# 03_-_ALIMENTACAO.net
KiCad netlist of a schematic drawn in Altium Designer
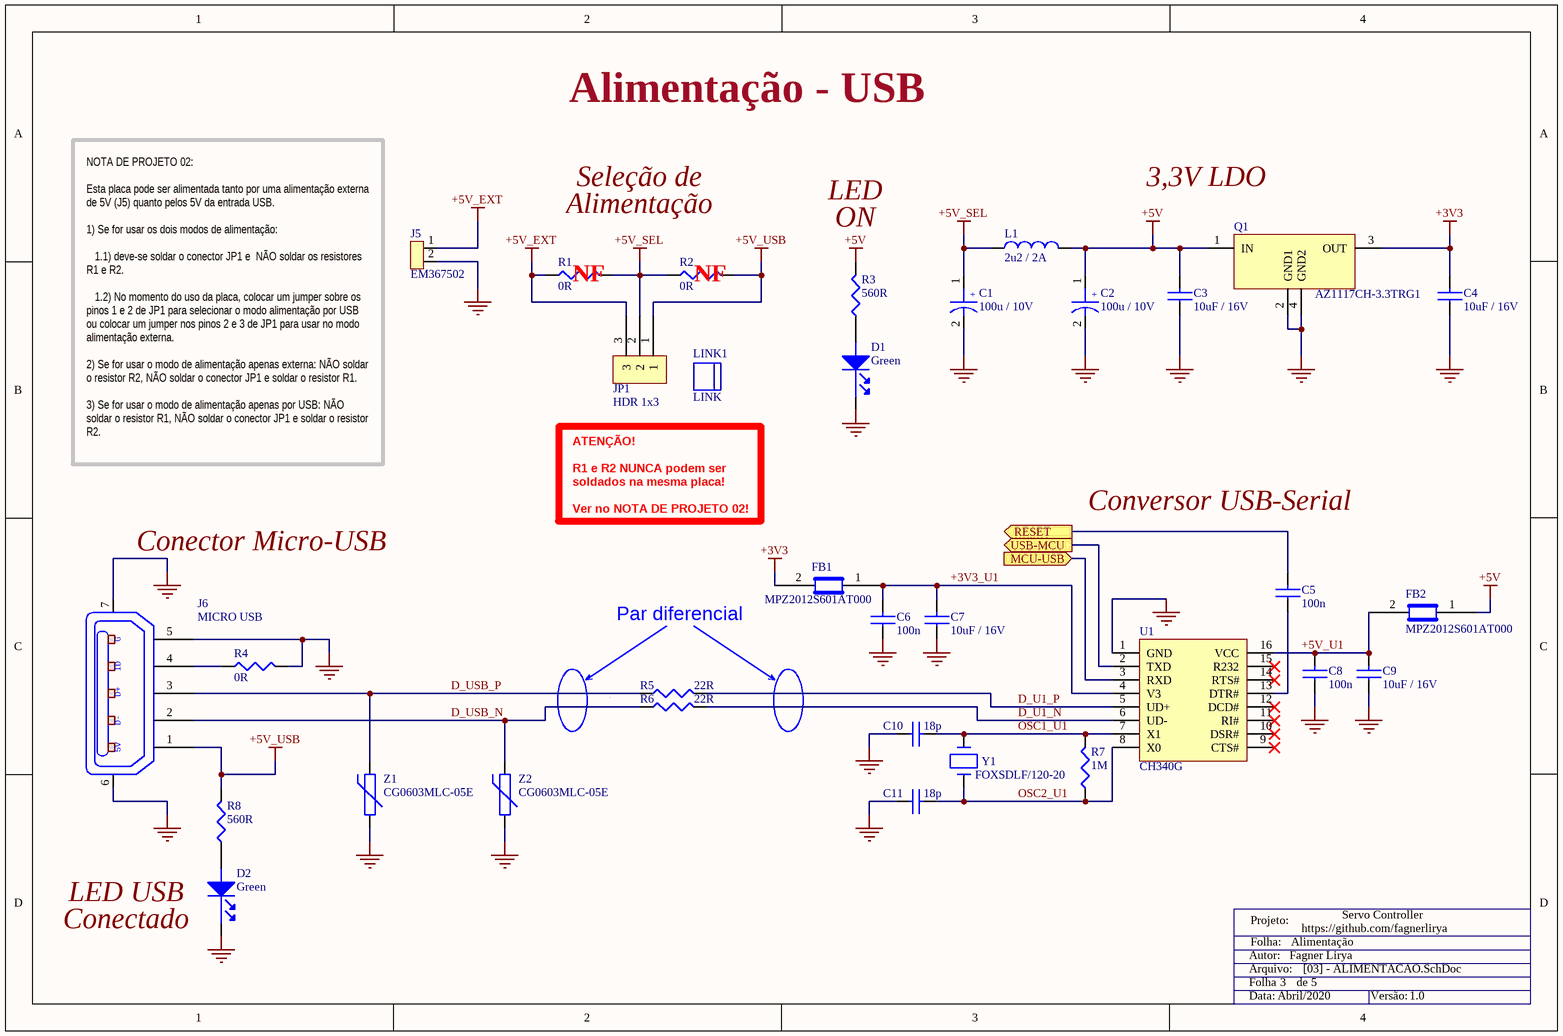
[diagram p0: [03] - ALIMENTACAO.SchDoc]

(export (version "E")
  (design (tool "Eeschema 10.0.6"))
  (components
    (comp (ref "C1")
      (value "100u / 10V")
      (footprint "C_ALU_C_SIZE")
      (description "CAP ALUM 100UF 20% 10V SMD")
      (fields
        (field (name "MANUFACTURER") "Panasonic Electronic Components")
        (field (name "MANUFACTURER PART NUMBER") "EEE-1AA101WR")
      )
      (libsource (lib "Servo_Control_Lib") (part "EEE-1AA101WR"))
    )
    (comp (ref "C2")
      (value "100u / 10V")
      (footprint "C_ALU_C_SIZE")
      (description "CAP ALUM 100UF 20% 10V SMD")
      (fields
        (field (name "MANUFACTURER") "Panasonic Electronic Components")
        (field (name "MANUFACTURER PART NUMBER") "EEE-1AA101WR")
      )
      (libsource (lib "Servo_Control_Lib") (part "EEE-1AA101WR"))
    )
    (comp (ref "C3")
      (value "10uF / 16V")
      (footprint "C0805")
      (description "CAP CER 10UF 16V X5R 0805")
      (fields
        (field (name "MANUFACTURER") "TDK Corporation")
        (field (name "MANUFACTURER PART NUMBER") "C2012X5R1C106M125AC")
      )
      (libsource (lib "Servo_Control_Lib") (part "C2012X5R1C106M125AC"))
    )
    (comp (ref "C4")
      (value "10uF / 16V")
      (footprint "C0805")
      (description "CAP CER 10UF 16V X5R 0805")
      (fields
        (field (name "MANUFACTURER") "TDK Corporation")
        (field (name "MANUFACTURER PART NUMBER") "C2012X5R1C106M125AC")
      )
      (libsource (lib "Servo_Control_Lib") (part "C2012X5R1C106M125AC"))
    )
    (comp (ref "C5")
      (value "100n")
      (footprint "C0805")
      (description "CAP CER 0.1UF 50V X7R 0805")
      (fields
        (field (name "MANUFACTURER") "TDK Corporation")
        (field (name "MANUFACTURER PART NUMBER") "C2012X7R1H104K085AA")
      )
      (libsource (lib "Servo_Control_Lib") (part "C2012X7R1H104K085AA_1"))
    )
    (comp (ref "C6")
      (value "100n")
      (footprint "C0805")
      (description "CAP CER 0.1UF 50V X7R 0805")
      (fields
        (field (name "MANUFACTURER") "TDK Corporation")
        (field (name "MANUFACTURER PART NUMBER") "C2012X7R1H104K085AA")
      )
      (libsource (lib "Servo_Control_Lib") (part "C2012X7R1H104K085AA_1"))
    )
    (comp (ref "C7")
      (value "10uF / 16V")
      (footprint "C0805")
      (description "CAP CER 10UF 16V X5R 0805")
      (fields
        (field (name "MANUFACTURER") "TDK Corporation")
        (field (name "MANUFACTURER PART NUMBER") "C2012X5R1C106M125AC")
      )
      (libsource (lib "Servo_Control_Lib") (part "C2012X5R1C106M125AC"))
    )
    (comp (ref "C8")
      (value "100n")
      (footprint "C0805")
      (description "CAP CER 0.1UF 50V X7R 0805")
      (fields
        (field (name "MANUFACTURER") "TDK Corporation")
        (field (name "MANUFACTURER PART NUMBER") "C2012X7R1H104K085AA")
      )
      (libsource (lib "Servo_Control_Lib") (part "C2012X7R1H104K085AA_1"))
    )
    (comp (ref "C9")
      (value "10uF / 16V")
      (footprint "C0805")
      (description "CAP CER 10UF 16V X5R 0805")
      (fields
        (field (name "MANUFACTURER") "TDK Corporation")
        (field (name "MANUFACTURER PART NUMBER") "C2012X5R1C106M125AC")
      )
      (libsource (lib "Servo_Control_Lib") (part "C2012X5R1C106M125AC"))
    )
    (comp (ref "C10")
      (value "18p")
      (footprint "C0805")
      (description "CAP CER 18PF 50V NP0 0805")
      (fields
        (field (name "MANUFACTURER") "Kemet")
        (field (name "MANUFACTURER PART NUMBER") "C0805C180J5GACTU")
      )
      (libsource (lib "Servo_Control_Lib") (part "C0805C180J5GACTU"))
    )
    (comp (ref "C11")
      (value "18p")
      (footprint "C0805")
      (description "CAP CER 18PF 50V NP0 0805")
      (fields
        (field (name "MANUFACTURER") "Kemet")
        (field (name "MANUFACTURER PART NUMBER") "C0805C180J5GACTU")
      )
      (libsource (lib "Servo_Control_Lib") (part "C0805C180J5GACTU"))
    )
    (comp (ref "D1")
      (value "Green")
      (footprint "LED_0603")
      (description "LED GREEN DIFFUSED 0603 SMD")
      (fields
        (field (name "MANUFACTURER") "OSRAM Opto Semiconductors Inc.")
        (field (name "MANUFACTURER PART NUMBER") "LG L29K-G2J1-24-Z")
      )
      (libsource (lib "Servo_Control_Lib") (part "LG L29K-G2J1-24-Z"))
    )
    (comp (ref "D2")
      (value "Green")
      (footprint "LED_0603")
      (description "LED GREEN DIFFUSED 0603 SMD")
      (fields
        (field (name "MANUFACTURER") "OSRAM Opto Semiconductors Inc.")
        (field (name "MANUFACTURER PART NUMBER") "LG L29K-G2J1-24-Z")
      )
      (libsource (lib "Servo_Control_Lib") (part "LG L29K-G2J1-24-Z"))
    )
    (comp (ref "FB1")
      (value "MPZ2012S601AT000")
      (footprint "C0805")
      (description "FERRITE CHIP BEAD 600 OHM SMD")
      (fields (field (name "MANUFACTURER") "TDK Corporation"))
      (libsource (lib "Servo_Control_Lib") (part "MPZ2012S601AT000"))
    )
    (comp (ref "FB2")
      (value "MPZ2012S601AT000")
      (footprint "C0805")
      (description "FERRITE CHIP BEAD 600 OHM SMD")
      (fields (field (name "MANUFACTURER") "TDK Corporation"))
      (libsource (lib "Servo_Control_Lib") (part "MPZ2012S601AT000"))
    )
    (comp (ref "J5")
      (value "EM367502")
      (footprint "2_Pins_Fixed_Terminal")
      (description "Fixed Terminal Blocks EURO (MA311-50002) TERM")
      (fields (field (name "MANUFACTURER") "Bussmann / Eaton"))
      (libsource (lib "Servo_Control_Lib") (part "EM367502"))
    )
    (comp (ref "J6")
      (value "MICRO USB")
      (footprint "USB_ML")
      (description "CONN USB MICRO B RECPT SMT R/A")
      (fields (field (name "MANUFACTURER") "??") (field (name "MANUFACTURER PART NUMBER") "ML-01"))
      (libsource (lib "Servo_Control_Lib") (part "USB-ML"))
    )
    (comp (ref "JP1")
      (value "HDR 1x3")
      (footprint "Hdr_1x3_2.54mm")
      (description "BERGSTIK II .100\" SR STRAIGHT")
      (fields (field (name "MANUFACTURER") "FCI") (field (name "MANUFACTURER PART NUMBER") "68000-103HLF"))
      (libsource (lib "Servo_Control_Lib") (part "68000-103HLF"))
    )
    (comp (ref "L1")
      (value "2u2 / 2A")
      (footprint "C1210_IND")
      (description "FIXED IND 2.2UH 2A 80 MOHM SMD")
      (fields
        (field (name "MANUFACTURER") "Kemet")
        (field (name "MANUFACTURER PART NUMBER") "L1210R2R2MDWIT")
      )
      (libsource (lib "Servo_Control_Lib") (part "L1210R2R2MDWIT"))
    )
    (comp (ref "LINK1")
      (value "LINK")
      (description "CONN JUMPER SHORTING .100\" GOLD")
      (fields
        (field (name "MANUFACTURER") "Sullins Connector Solutions")
        (field (name "MANUFACTURER PART NUMBER") "QPC02SXGN-RC")
      )
      (libsource (lib "Servo_Control_Lib") (part "QPC02SXGN-RC"))
    )
    (comp (ref "Q1")
      (value "AZ1117CH-3.3TRG1")
      (footprint "SOT223")
      (description "LDO Voltage Regulators LDO BJT HiCurr 1.15V at 1A")
      (fields (field (name "MANUFACTURER") "Diodes Incorporated"))
      (libsource (lib "Servo_Control_Lib") (part "AZ1117CH-3.3TRG1"))
    )
    (comp (ref "R1")
      (value "0R")
      (footprint "R0805")
      (description "RES SMD 0.0 OHM JUMPER 1/8W 0805")
      (fields
        (field (name "MANUFACTURER") "Yageo")
        (field (name "MANUFACTURER PART NUMBER") "RC0805JR-070RL")
      )
      (libsource (lib "Servo_Control_Lib") (part "RC0805JR-070RL"))
    )
    (comp (ref "R2")
      (value "0R")
      (footprint "R0805")
      (description "RES SMD 0.0 OHM JUMPER 1/8W 0805")
      (fields
        (field (name "MANUFACTURER") "Yageo")
        (field (name "MANUFACTURER PART NUMBER") "RC0805JR-070RL")
      )
      (libsource (lib "Servo_Control_Lib") (part "RC0805JR-070RL"))
    )
    (comp (ref "R3")
      (value "560R")
      (footprint "R0805")
      (description "RES SMD 560 OHM 1% 1/8W 0805")
      (fields
        (field (name "MANUFACTURER") "Yageo")
        (field (name "MANUFACTURER PART NUMBER") "RC0805FR-07560RL")
      )
      (libsource (lib "Servo_Control_Lib") (part "RC0805FR-07560RL"))
    )
    (comp (ref "R4")
      (value "0R")
      (footprint "R0805")
      (description "RES SMD 0.0 OHM JUMPER 1/8W 0805")
      (fields
        (field (name "MANUFACTURER") "Yageo")
        (field (name "MANUFACTURER PART NUMBER") "RC0805JR-070RL")
      )
      (libsource (lib "Servo_Control_Lib") (part "RC0805JR-070RL"))
    )
    (comp (ref "R5")
      (value "22R")
      (footprint "R0805")
      (description "RES SMD 22 OHM 1% 1/8W 0805")
      (fields
        (field (name "MANUFACTURER") "Yageo")
        (field (name "MANUFACTURER PART NUMBER") "RC0805FR-0722RL")
      )
      (libsource (lib "Servo_Control_Lib") (part "RC0805FR-0722RL"))
    )
    (comp (ref "R6")
      (value "22R")
      (footprint "R0805")
      (description "RES SMD 22 OHM 1% 1/8W 0805")
      (fields
        (field (name "MANUFACTURER") "Yageo")
        (field (name "MANUFACTURER PART NUMBER") "RC0805FR-0722RL")
      )
      (libsource (lib "Servo_Control_Lib") (part "RC0805FR-0722RL"))
    )
    (comp (ref "R7")
      (value "1M")
      (footprint "R0805")
      (description "RES SMD 1M OHM 1% 1/8W 0805")
      (fields
        (field (name "MANUFACTURER") "Yageo")
        (field (name "MANUFACTURER PART NUMBER") "RC0805FR-071ML")
      )
      (libsource (lib "Servo_Control_Lib") (part "RC0805FR-071ML"))
    )
    (comp (ref "R8")
      (value "560R")
      (footprint "R0805")
      (description "RES SMD 560 OHM 1% 1/8W 0805")
      (fields
        (field (name "MANUFACTURER") "Yageo")
        (field (name "MANUFACTURER PART NUMBER") "RC0805FR-07560RL")
      )
      (libsource (lib "Servo_Control_Lib") (part "RC0805FR-07560RL"))
    )
    (comp (ref "TitleBlock2")
      (value "Title Block")
      (libsource (lib "Servo_Control_Lib") (part "Title Block"))
    )
    (comp (ref "U1")
      (value "CH340G")
      (footprint "SO-16")
      (description "USB bus adapters")
      (fields (field (name "MANUFACTURER") "Chinese"))
      (libsource (lib "Servo_Control_Lib") (part "CH340G"))
    )
    (comp (ref "Y1")
      (value "FOXSDLF/120-20")
      (footprint "HC49SD")
      (description "Crystals 12MHz 20pF")
      (fields (field (name "MANUFACTURER") "Fox") (field (name "TOLERANCE") "50 PPM"))
      (libsource (lib "Servo_Control_Lib") (part "FOXSDLF/120-20"))
    )
    (comp (ref "Z1")
      (value "CG0603MLC-05E")
      (footprint "R0603")
      (description "VARISTOR 0603")
      (fields (field (name "MANUFACTURER") "Bourns Inc."))
      (libsource (lib "Servo_Control_Lib") (part "CG0603MLC-05E"))
    )
    (comp (ref "Z2")
      (value "CG0603MLC-05E")
      (footprint "R0603")
      (description "VARISTOR 0603")
      (fields (field (name "MANUFACTURER") "Bourns Inc."))
      (libsource (lib "Servo_Control_Lib") (part "CG0603MLC-05E"))
    )
  )
  (nets
    (net (code "1") (name "+3V3") (class "Default")
      (node (ref "C4") (pin "2") (pinfunction "2_2") (pintype "passive"))
      (node (ref "FB1") (pin "2") (pinfunction "2_2") (pintype "passive"))
      (node (ref "Q1") (pin "3") (pinfunction "OUT_3") (pintype "passive"))
    )
    (net (code "2") (name "+5V") (class "Default")
      (node (ref "C2") (pin "1") (pinfunction "1_1") (pintype "passive"))
      (node (ref "C3") (pin "2") (pinfunction "2_2") (pintype "passive"))
      (node (ref "FB2") (pin "1") (pinfunction "1_1") (pintype "passive"))
      (node (ref "L1") (pin "2") (pinfunction "2_2") (pintype "passive"))
      (node (ref "Q1") (pin "1") (pinfunction "IN_1") (pintype "passive"))
      (node (ref "R3") (pin "2") (pinfunction "2_2") (pintype "passive"))
    )
    (net (code "3") (name "+5V_EXT") (class "Default")
      (node (ref "J5") (pin "1") (pinfunction "1_1") (pintype "passive"))
      (node (ref "JP1") (pin "3") (pinfunction "3_3") (pintype "passive"))
      (node (ref "R1") (pin "1") (pinfunction "1_1") (pintype "passive"))
    )
    (net (code "4") (name "+5V_SEL") (class "Default")
      (node (ref "C1") (pin "1") (pinfunction "1_1") (pintype "passive"))
      (node (ref "JP1") (pin "2") (pinfunction "2_2") (pintype "passive"))
      (node (ref "L1") (pin "1") (pinfunction "1_1") (pintype "passive"))
      (node (ref "R1") (pin "2") (pinfunction "2_2") (pintype "passive"))
      (node (ref "R2") (pin "1") (pinfunction "1_1") (pintype "passive"))
    )
    (net (code "5") (name "+5V_USB") (class "Default")
      (node (ref "J6") (pin "1") (pinfunction "1_1") (pintype "passive"))
      (node (ref "JP1") (pin "1") (pinfunction "1_1") (pintype "passive"))
      (node (ref "R2") (pin "2") (pinfunction "2_2") (pintype "passive"))
      (node (ref "R8") (pin "2") (pinfunction "2_2") (pintype "passive"))
    )
    (net (code "6") (name "/+3V3_U1") (class "Default")
      (node (ref "C6") (pin "2") (pinfunction "2_2") (pintype "passive"))
      (node (ref "C7") (pin "2") (pinfunction "2_2") (pintype "passive"))
      (node (ref "FB1") (pin "1") (pinfunction "1_1") (pintype "passive"))
      (node (ref "U1") (pin "4") (pinfunction "V3_4") (pintype "passive"))
    )
    (net (code "7") (name "/+5V_U1") (class "Default")
      (node (ref "C8") (pin "2") (pinfunction "2_2") (pintype "passive"))
      (node (ref "C9") (pin "2") (pinfunction "2_2") (pintype "passive"))
      (node (ref "FB2") (pin "2") (pinfunction "2_2") (pintype "passive"))
      (node (ref "U1") (pin "16") (pinfunction "VCC_16") (pintype "passive"))
    )
    (net (code "8") (name "/D_U1_N") (class "Default")
      (node (ref "R6") (pin "2") (pinfunction "2_2") (pintype "passive"))
      (node (ref "U1") (pin "6") (pinfunction "UD-_6") (pintype "passive"))
    )
    (net (code "9") (name "/D_U1_P") (class "Default")
      (node (ref "R5") (pin "2") (pinfunction "2_2") (pintype "passive"))
      (node (ref "U1") (pin "5") (pinfunction "UD+_5") (pintype "passive"))
    )
    (net (code "10") (name "/D_USB_N") (class "Default")
      (node (ref "J6") (pin "2") (pinfunction "2_2") (pintype "passive"))
      (node (ref "R6") (pin "1") (pinfunction "1_1") (pintype "passive"))
      (node (ref "Z2") (pin "2") (pinfunction "2_2") (pintype "passive"))
    )
    (net (code "11") (name "/D_USB_P") (class "Default")
      (node (ref "J6") (pin "3") (pinfunction "3_3") (pintype "passive"))
      (node (ref "R5") (pin "1") (pinfunction "1_1") (pintype "passive"))
      (node (ref "Z1") (pin "2") (pinfunction "2_2") (pintype "passive"))
    )
    (net (code "12") (name "/MCU-USB") (class "Default")
      (node (ref "U1") (pin "3") (pinfunction "RXD_3") (pintype "passive"))
    )
    (net (code "13") (name "/OSC1_U1") (class "Default")
      (node (ref "C10") (pin "2") (pinfunction "2_2") (pintype "passive"))
      (node (ref "R7") (pin "2") (pinfunction "2_2") (pintype "passive"))
      (node (ref "U1") (pin "7") (pinfunction "X1_7") (pintype "passive"))
      (node (ref "Y1") (pin "2") (pinfunction "2_2") (pintype "passive"))
    )
    (net (code "14") (name "/OSC2_U1") (class "Default")
      (node (ref "C11") (pin "2") (pinfunction "2_2") (pintype "passive"))
      (node (ref "R7") (pin "1") (pinfunction "1_1") (pintype "passive"))
      (node (ref "U1") (pin "8") (pinfunction "X0_8") (pintype "passive"))
      (node (ref "Y1") (pin "1") (pinfunction "1_1") (pintype "passive"))
    )
    (net (code "15") (name "/RESET") (class "Default")
      (node (ref "C5") (pin "2") (pinfunction "2_2") (pintype "passive"))
    )
    (net (code "16") (name "/USB-MCU") (class "Default")
      (node (ref "U1") (pin "2") (pinfunction "TXD_2") (pintype "passive"))
    )
    (net (code "17") (name "GND") (class "Default")
      (node (ref "C1") (pin "2") (pinfunction "2_2") (pintype "passive"))
      (node (ref "C10") (pin "1") (pinfunction "1_1") (pintype "passive"))
      (node (ref "C11") (pin "1") (pinfunction "1_1") (pintype "passive"))
      (node (ref "C2") (pin "2") (pinfunction "2_2") (pintype "passive"))
      (node (ref "C3") (pin "1") (pinfunction "1_1") (pintype "passive"))
      (node (ref "C4") (pin "1") (pinfunction "1_1") (pintype "passive"))
      (node (ref "C6") (pin "1") (pinfunction "1_1") (pintype "passive"))
      (node (ref "C7") (pin "1") (pinfunction "1_1") (pintype "passive"))
      (node (ref "C8") (pin "1") (pinfunction "1_1") (pintype "passive"))
      (node (ref "C9") (pin "1") (pinfunction "1_1") (pintype "passive"))
      (node (ref "D1") (pin "1") (pinfunction "Cathode_1") (pintype "passive"))
      (node (ref "D2") (pin "1") (pinfunction "Cathode_1") (pintype "passive"))
      (node (ref "J5") (pin "2") (pinfunction "2_2") (pintype "passive"))
      (node (ref "J6") (pin "5") (pinfunction "5_5") (pintype "passive"))
      (node (ref "J6") (pin "6") (pinfunction "6_6") (pintype "passive"))
      (node (ref "J6") (pin "7") (pinfunction "7_7") (pintype "passive"))
      (node (ref "Q1") (pin "2") (pinfunction "GND1_2") (pintype "passive"))
      (node (ref "Q1") (pin "4") (pinfunction "GND2_4") (pintype "passive"))
      (node (ref "R4") (pin "2") (pinfunction "2_2") (pintype "passive"))
      (node (ref "U1") (pin "1") (pinfunction "GND_1") (pintype "passive"))
      (node (ref "Z1") (pin "1") (pinfunction "1_1") (pintype "passive"))
      (node (ref "Z2") (pin "1") (pinfunction "1_1") (pintype "passive"))
    )
    (net (code "18") (name "Net-(D1-Anode)") (class "Default")
      (node (ref "D1") (pin "2") (pinfunction "Anode_2") (pintype "passive"))
      (node (ref "R3") (pin "1") (pinfunction "1_1") (pintype "passive"))
    )
    (net (code "19") (name "Net-(D2-Anode)") (class "Default")
      (node (ref "D2") (pin "2") (pinfunction "Anode_2") (pintype "passive"))
      (node (ref "R8") (pin "1") (pinfunction "1_1") (pintype "passive"))
    )
    (net (code "20") (name "Net-(J6-Pad4)") (class "Default")
      (node (ref "J6") (pin "4") (pinfunction "4_4") (pintype "passive"))
      (node (ref "R4") (pin "1") (pinfunction "1_1") (pintype "passive"))
    )
    (net (code "21") (name "Net-(U1-DTR#)") (class "Default")
      (node (ref "C5") (pin "1") (pinfunction "1_1") (pintype "passive"))
      (node (ref "U1") (pin "13") (pinfunction "DTR#_13") (pintype "passive"))
    )
    (net (code "22") (name "unconnected-(U1-CTS#-Pad9)") (class "Default")
      (node (ref "U1") (pin "9") (pinfunction "CTS#_9") (pintype "passive+no_connect"))
    )
    (net (code "23") (name "unconnected-(U1-DCD#-Pad12)") (class "Default")
      (node (ref "U1") (pin "12") (pinfunction "DCD#_12") (pintype "passive+no_connect"))
    )
    (net (code "24") (name "unconnected-(U1-DSR#-Pad10)") (class "Default")
      (node (ref "U1") (pin "10") (pinfunction "DSR#_10") (pintype "passive+no_connect"))
    )
    (net (code "25") (name "unconnected-(U1-R232-Pad15)") (class "Default")
      (node (ref "U1") (pin "15") (pinfunction "R232_15") (pintype "passive+no_connect"))
    )
    (net (code "26") (name "unconnected-(U1-RI#-Pad11)") (class "Default")
      (node (ref "U1") (pin "11") (pinfunction "RI#_11") (pintype "passive+no_connect"))
    )
    (net (code "27") (name "unconnected-(U1-RTS#-Pad14)") (class "Default")
      (node (ref "U1") (pin "14") (pinfunction "RTS#_14") (pintype "passive+no_connect"))
    )
  )
)
